# RAUPS_SingleLayer_Heater.net
KiCad netlist of a schematic drawn in EAGLE
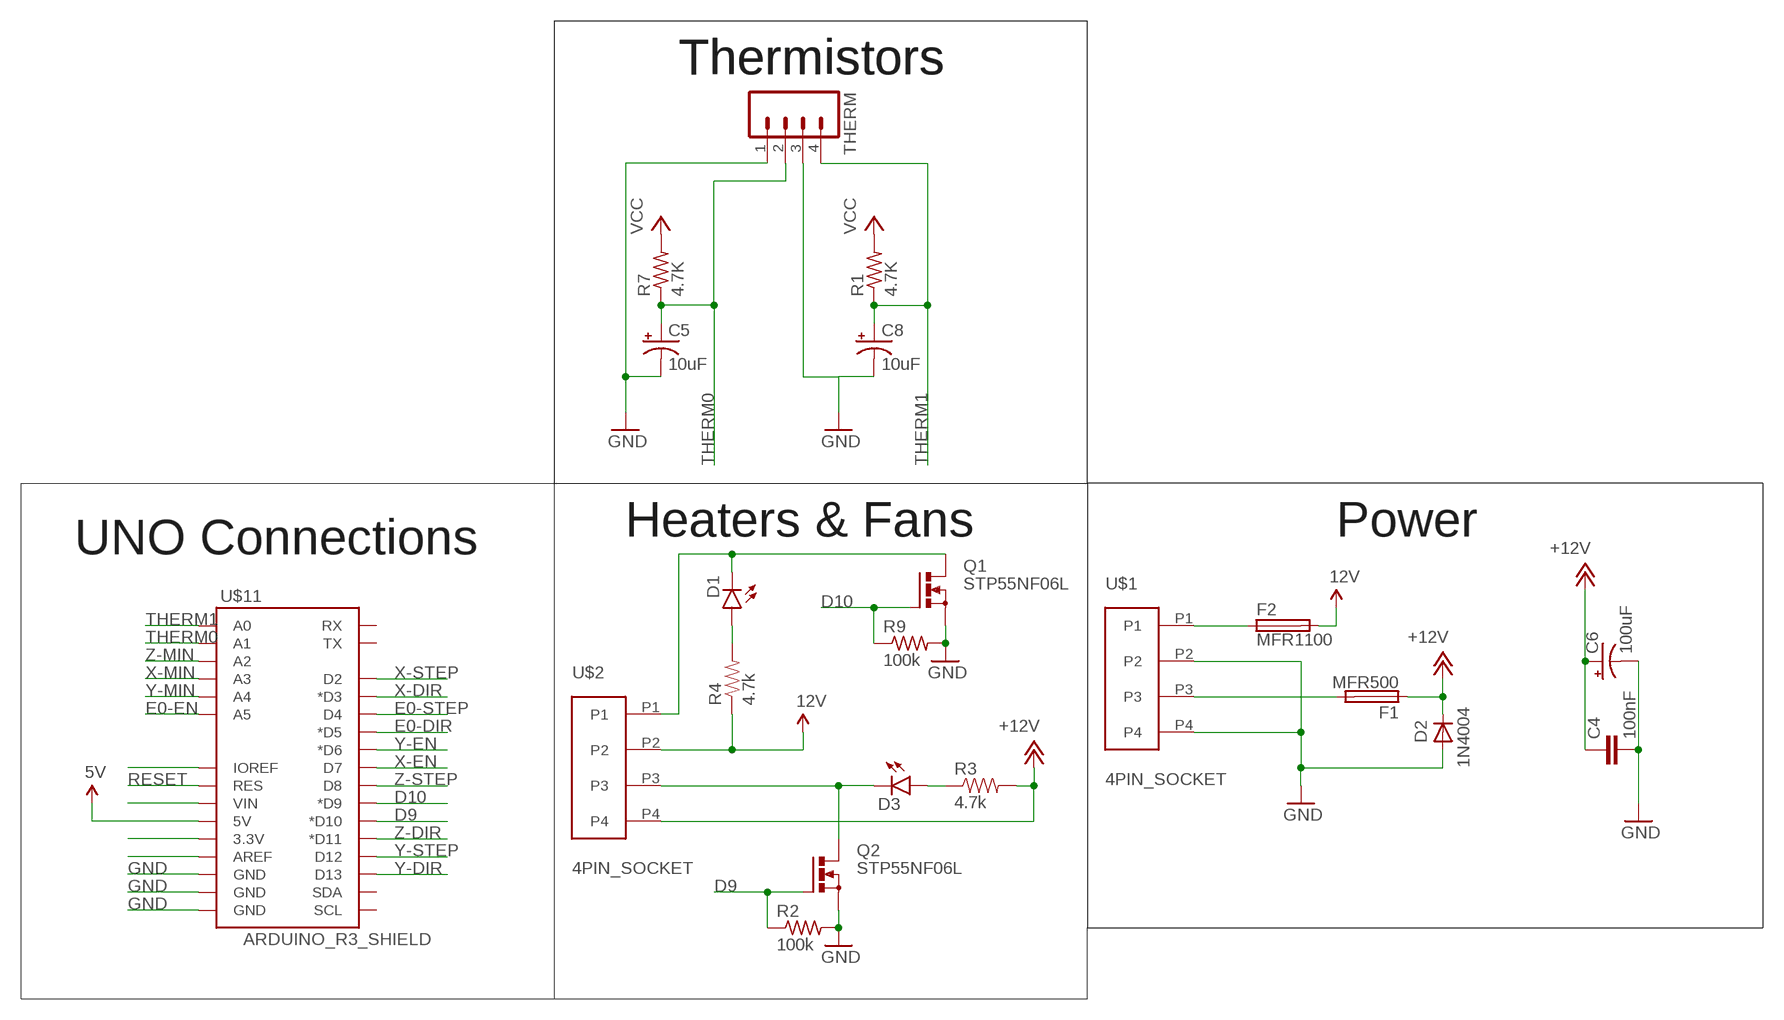
[diagram p0: schematic, sheet 1]

(export (version "E")
  (design (tool "Eeschema 10.0.6"))
  (components
    (comp (ref "C4")
      (value "100nF")
      (footprint "eagle-import:C2.5-3")
      (libsource (lib "eagle-import") (part "C2,5-3"))
    )
    (comp (ref "C5")
      (value "10uF")
      (footprint "eagle-import:E2,5-5")
      (libsource (lib "eagle-import") (part "CPOL-USE2.5-5"))
    )
    (comp (ref "C6")
      (value "100uF")
      (footprint "eagle-import:E3,5-8")
      (libsource (lib "eagle-import") (part "CPOL-USE3.5-8"))
    )
    (comp (ref "C8")
      (value "10uF")
      (footprint "eagle-import:E2,5-5")
      (libsource (lib "eagle-import") (part "CPOL-USE2.5-5"))
    )
    (comp (ref "D1")
      (value "LED-3MM-NO_SILK")
      (footprint "eagle-import:LED3MM-NS")
      (libsource (lib "eagle-import") (part "LED-3MM-NO_SILK"))
    )
    (comp (ref "D2")
      (value "1N4004")
      (footprint "eagle-import:DO41-10")
      (libsource (lib "eagle-import") (part "1N4004"))
    )
    (comp (ref "D3")
      (value "LED-3MM-NO_SILK")
      (footprint "eagle-import:LED3MM-NS")
      (libsource (lib "eagle-import") (part "LED-3MM-NO_SILK"))
    )
    (comp (ref "F1")
      (value "MFR500")
      (footprint "eagle-import:MFR500")
      (libsource (lib "eagle-import") (part "PTCFUSE"))
    )
    (comp (ref "F2")
      (value "MFR1100")
      (footprint "eagle-import:MFR1100")
      (libsource (lib "eagle-import") (part "PTCFUSEMFR1100"))
    )
    (comp (ref "Q1")
      (value "STP55NF06L")
      (footprint "eagle-import:TO220BV")
      (libsource (lib "eagle-import") (part "IRF512"))
    )
    (comp (ref "Q2")
      (value "STP55NF06L")
      (footprint "eagle-import:TO220BV")
      (libsource (lib "eagle-import") (part "IRF512"))
    )
    (comp (ref "R1")
      (value "4.7K")
      (footprint "eagle-import:0207_7")
      (libsource (lib "eagle-import") (part "R-US_0207/7"))
    )
    (comp (ref "R2")
      (value "100k")
      (footprint "eagle-import:0207_7")
      (libsource (lib "eagle-import") (part "R-US_0207/7"))
    )
    (comp (ref "R3")
      (value "4.7k")
      (footprint "eagle-import:AXIAL-0.3")
      (libsource (lib "eagle-import") (part "1KOHM-1/4W-5%(PTH)"))
    )
    (comp (ref "R4")
      (value "4.7k")
      (footprint "eagle-import:AXIAL-0.3")
      (libsource (lib "eagle-import") (part "1KOHM-1/4W-5%(PTH)"))
    )
    (comp (ref "R7")
      (value "4.7K")
      (footprint "eagle-import:0207_7")
      (libsource (lib "eagle-import") (part "R-US_0207/7"))
    )
    (comp (ref "R9")
      (value "100k")
      (footprint "eagle-import:0207_7")
      (libsource (lib "eagle-import") (part "R-US_0207/7"))
    )
    (comp (ref "THERM")
      (value "M04LONGPADS")
      (footprint "eagle-import:1X04_LONGPADS")
      (libsource (lib "eagle-import") (part "M04LONGPADS"))
    )
    (comp (ref "U$1")
      (value "4PIN_SOCKET")
      (footprint "eagle-import:CONN-4PIN")
      (libsource (lib "eagle-import") (part "4PIN_SOCKET"))
    )
    (comp (ref "U$2")
      (value "4PIN_SOCKET")
      (footprint "eagle-import:CONN-4PIN")
      (libsource (lib "eagle-import") (part "4PIN_SOCKET"))
    )
    (comp (ref "U$11")
      (value "ARDUINO_R3_SHIELD")
      (footprint "eagle-import:UNO_R3_SHIELD")
      (libsource (lib "eagle-import") (part "ARDUINO_R3_SHIELD"))
    )
  )
  (nets
    (net (code "1") (name "+12V") (class "Default")
      (node (ref "C4") (pin "1") (pinfunction "1_1") (pintype "passive"))
      (node (ref "C6") (pin "+") (pinfunction "+_+") (pintype "passive"))
      (node (ref "D2") (pin "C") (pinfunction "C_C") (pintype "passive"))
      (node (ref "F1") (pin "1") (pinfunction "1_1") (pintype "passive"))
      (node (ref "R3") (pin "P$2") (pinfunction "2_P$2") (pintype "passive"))
      (node (ref "U$2") (pin "P4") (pinfunction "P4_P4") (pintype "bidirectional"))
    )
    (net (code "2") (name "/D9") (class "Default")
      (node (ref "Q2") (pin "G") (pinfunction "G_G") (pintype "passive"))
      (node (ref "R2") (pin "1") (pinfunction "1_1") (pintype "passive"))
      (node (ref "U$11") (pin "D10") (pinfunction "*D10_D10") (pintype "bidirectional"))
    )
    (net (code "3") (name "/D10") (class "Default")
      (node (ref "Q1") (pin "G") (pinfunction "G_G") (pintype "passive"))
      (node (ref "R9") (pin "1") (pinfunction "1_1") (pintype "passive"))
      (node (ref "U$11") (pin "D9") (pinfunction "*D9_D9") (pintype "bidirectional"))
    )
    (net (code "4") (name "/E0-DIR") (class "Default")
      (node (ref "U$11") (pin "D5") (pinfunction "*D5_D5") (pintype "bidirectional"))
    )
    (net (code "5") (name "/E0-EN") (class "Default")
      (node (ref "U$11") (pin "A5") (pinfunction "A5_A5") (pintype "bidirectional"))
    )
    (net (code "6") (name "/E0-STEP") (class "Default")
      (node (ref "U$11") (pin "D4") (pinfunction "D4_D4") (pintype "bidirectional"))
    )
    (net (code "7") (name "/RESET") (class "Default")
      (node (ref "U$11") (pin "RES") (pinfunction "RES_RES") (pintype "bidirectional"))
    )
    (net (code "8") (name "/THERM0") (class "Default")
      (node (ref "C5") (pin "+") (pinfunction "+_+") (pintype "passive"))
      (node (ref "R7") (pin "1") (pinfunction "1_1") (pintype "passive"))
      (node (ref "THERM") (pin "2") (pinfunction "2_2") (pintype "passive"))
      (node (ref "U$11") (pin "A1") (pinfunction "A1_A1") (pintype "bidirectional"))
    )
    (net (code "9") (name "/THERM1") (class "Default")
      (node (ref "C8") (pin "+") (pinfunction "+_+") (pintype "passive"))
      (node (ref "R1") (pin "1") (pinfunction "1_1") (pintype "passive"))
      (node (ref "THERM") (pin "4") (pinfunction "4_4") (pintype "passive"))
      (node (ref "U$11") (pin "A0") (pinfunction "A0_A0") (pintype "bidirectional"))
    )
    (net (code "10") (name "/X-DIR") (class "Default")
      (node (ref "U$11") (pin "D3") (pinfunction "*D3_D3") (pintype "bidirectional"))
    )
    (net (code "11") (name "/X-EN") (class "Default")
      (node (ref "U$11") (pin "D7") (pinfunction "D7_D7") (pintype "bidirectional"))
    )
    (net (code "12") (name "/X-MIN") (class "Default")
      (node (ref "U$11") (pin "A3") (pinfunction "A3_A3") (pintype "bidirectional"))
    )
    (net (code "13") (name "/X-STEP") (class "Default")
      (node (ref "U$11") (pin "D2") (pinfunction "D2_D2") (pintype "bidirectional"))
    )
    (net (code "14") (name "/Y-DIR") (class "Default")
      (node (ref "U$11") (pin "D13") (pinfunction "D13_D13") (pintype "bidirectional"))
    )
    (net (code "15") (name "/Y-EN") (class "Default")
      (node (ref "U$11") (pin "D6") (pinfunction "*D6_D6") (pintype "bidirectional"))
    )
    (net (code "16") (name "/Y-MIN") (class "Default")
      (node (ref "U$11") (pin "A4") (pinfunction "A4_A4") (pintype "bidirectional"))
    )
    (net (code "17") (name "/Y-STEP") (class "Default")
      (node (ref "U$11") (pin "D12") (pinfunction "D12_D12") (pintype "bidirectional"))
    )
    (net (code "18") (name "/Z-DIR") (class "Default")
      (node (ref "U$11") (pin "D11") (pinfunction "*D11_D11") (pintype "bidirectional"))
    )
    (net (code "19") (name "/Z-MIN") (class "Default")
      (node (ref "U$11") (pin "A2") (pinfunction "A2_A2") (pintype "bidirectional"))
    )
    (net (code "20") (name "/Z-STEP") (class "Default")
      (node (ref "U$11") (pin "D8") (pinfunction "D8_D8") (pintype "bidirectional"))
    )
    (net (code "21") (name "5V") (class "Default")
      (node (ref "U$11") (pin "5V") (pinfunction "5V_5V") (pintype "bidirectional"))
    )
    (net (code "22") (name "12V") (class "Default")
      (node (ref "F2") (pin "2") (pinfunction "2_2") (pintype "passive"))
      (node (ref "R4") (pin "P$1") (pinfunction "1_P$1") (pintype "passive"))
      (node (ref "U$2") (pin "P2") (pinfunction "P2_P2") (pintype "bidirectional"))
    )
    (net (code "23") (name "GND") (class "Default")
      (node (ref "C4") (pin "2") (pinfunction "2_2") (pintype "passive"))
      (node (ref "C5") (pin "-") (pinfunction "-_-") (pintype "passive"))
      (node (ref "C6") (pin "-") (pinfunction "-_-") (pintype "passive"))
      (node (ref "C8") (pin "-") (pinfunction "-_-") (pintype "passive"))
      (node (ref "D2") (pin "A") (pinfunction "A_A") (pintype "passive"))
      (node (ref "Q1") (pin "S") (pinfunction "S_S") (pintype "passive"))
      (node (ref "Q2") (pin "S") (pinfunction "S_S") (pintype "passive"))
      (node (ref "R2") (pin "2") (pinfunction "2_2") (pintype "passive"))
      (node (ref "R9") (pin "2") (pinfunction "2_2") (pintype "passive"))
      (node (ref "THERM") (pin "1") (pinfunction "1_1") (pintype "passive"))
      (node (ref "THERM") (pin "3") (pinfunction "3_3") (pintype "passive"))
      (node (ref "U$1") (pin "P2") (pinfunction "P2_P2") (pintype "bidirectional"))
      (node (ref "U$1") (pin "P4") (pinfunction "P4_P4") (pintype "bidirectional"))
      (node (ref "U$11") (pin "GND@0") (pinfunction "GND_GND@0") (pintype "bidirectional"))
      (node (ref "U$11") (pin "GND@1") (pinfunction "GND_GND@1") (pintype "bidirectional"))
      (node (ref "U$11") (pin "GND@2") (pinfunction "GND_GND@2") (pintype "bidirectional"))
    )
    (net (code "24") (name "Net-(D1-C)") (class "Default")
      (node (ref "D1") (pin "K") (pinfunction "C_K") (pintype "passive"))
      (node (ref "Q1") (pin "D") (pinfunction "D_D") (pintype "passive"))
      (node (ref "U$2") (pin "P1") (pinfunction "P1_P1") (pintype "bidirectional"))
    )
    (net (code "25") (name "Net-(D3-C)") (class "Default")
      (node (ref "D3") (pin "K") (pinfunction "C_K") (pintype "passive"))
      (node (ref "Q2") (pin "D") (pinfunction "D_D") (pintype "passive"))
      (node (ref "U$2") (pin "P3") (pinfunction "P3_P3") (pintype "bidirectional"))
    )
    (net (code "26") (name "Net-(F1-Pad2)") (class "Default")
      (node (ref "F1") (pin "2") (pinfunction "2_2") (pintype "passive"))
      (node (ref "U$1") (pin "P3") (pinfunction "P3_P3") (pintype "bidirectional"))
    )
    (net (code "27") (name "Net-(F2-Pad1)") (class "Default")
      (node (ref "F2") (pin "1") (pinfunction "1_1") (pintype "passive"))
      (node (ref "U$1") (pin "P1") (pinfunction "P1_P1") (pintype "bidirectional"))
    )
    (net (code "28") (name "Net-(R3-1)") (class "Default")
      (node (ref "D3") (pin "A") (pinfunction "A_A") (pintype "passive"))
      (node (ref "R3") (pin "P$1") (pinfunction "1_P$1") (pintype "passive"))
    )
    (net (code "29") (name "Net-(R4-2)") (class "Default")
      (node (ref "D1") (pin "A") (pinfunction "A_A") (pintype "passive"))
      (node (ref "R4") (pin "P$2") (pinfunction "2_P$2") (pintype "passive"))
    )
    (net (code "30") (name "VCC") (class "Default")
      (node (ref "R1") (pin "2") (pinfunction "2_2") (pintype "passive"))
      (node (ref "R7") (pin "2") (pinfunction "2_2") (pintype "passive"))
    )
    (net (code "31") (name "unconnected-(U$11-Pad3.3V)") (class "Default")
      (node (ref "U$11") (pin "3.3V") (pinfunction "3.3V_3.3V") (pintype "bidirectional"))
    )
    (net (code "32") (name "unconnected-(U$11-PadAREF)") (class "Default")
      (node (ref "U$11") (pin "AREF") (pinfunction "AREF_AREF") (pintype "bidirectional"))
    )
    (net (code "33") (name "unconnected-(U$11-PadIOREF)") (class "Default")
      (node (ref "U$11") (pin "IOREF") (pinfunction "IOREF_IOREF") (pintype "bidirectional"))
    )
    (net (code "34") (name "unconnected-(U$11-PadRX)") (class "Default")
      (node (ref "U$11") (pin "RX") (pinfunction "RX_RX") (pintype "bidirectional"))
    )
    (net (code "35") (name "unconnected-(U$11-PadSCL)") (class "Default")
      (node (ref "U$11") (pin "SCL") (pinfunction "SCL_SCL") (pintype "bidirectional"))
    )
    (net (code "36") (name "unconnected-(U$11-PadSDA)") (class "Default")
      (node (ref "U$11") (pin "SDA") (pinfunction "SDA_SDA") (pintype "bidirectional"))
    )
    (net (code "37") (name "unconnected-(U$11-PadTX)") (class "Default")
      (node (ref "U$11") (pin "TX") (pinfunction "TX_TX") (pintype "bidirectional"))
    )
    (net (code "38") (name "unconnected-(U$11-PadVIN)") (class "Default")
      (node (ref "U$11") (pin "VIN") (pinfunction "VIN_VIN") (pintype "bidirectional"))
    )
  )
)
